# LVRegulation.net
KiCad netlist of a schematic drawn in Altium Designer
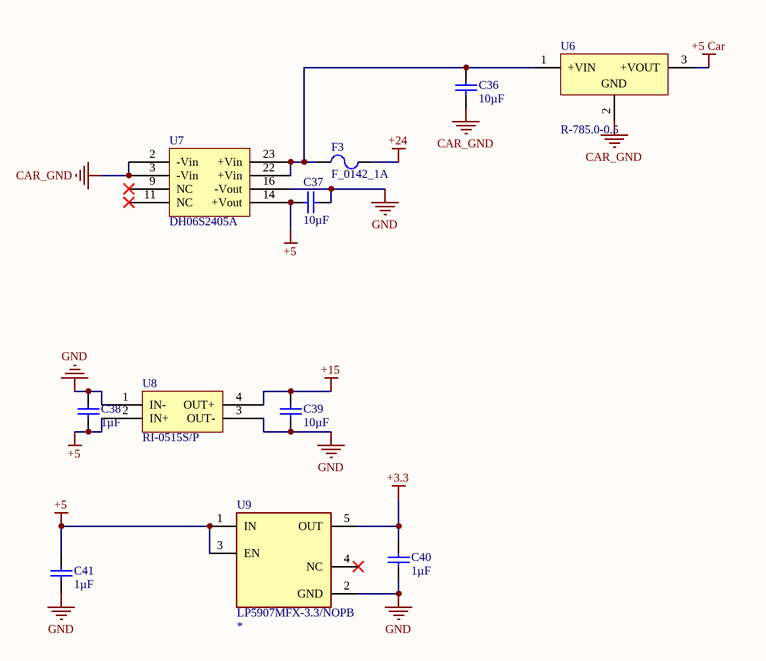
[diagram p0: LVRegulation.SchDoc]

(export (version "E")
  (design (tool "Eeschema 10.0.6"))
  (components
    (comp (ref "C36")
      (value "10µF")
      (footprint "1210_Capacitor")
      (description "Cap Cerem 10uF 10% 50V")
      (fields (field (name "TOLERANCE") "10%"))
      (libsource (lib "University of Minnesota - Solar Vehicle Project") (part "Cap"))
    )
    (comp (ref "C37")
      (value "10µF")
      (footprint "1210_Capacitor")
      (description "Cap Cerem 10uF 10% 50V")
      (fields (field (name "TOLERANCE") "10%"))
      (libsource (lib "University of Minnesota - Solar Vehicle Project") (part "Cap"))
    )
    (comp (ref "C38")
      (value "1µF")
      (footprint "0805_Capacitor")
      (description "CAP 0805 1uF 50V")
      (fields (field (name "TOLERANCE") "10%"))
      (libsource (lib "University of Minnesota - Solar Vehicle Project") (part "Cap"))
    )
    (comp (ref "C39")
      (value "10µF")
      (footprint "1210_Capacitor")
      (description "Cap Cerem 10uF 10% 50V")
      (fields (field (name "TOLERANCE") "10%"))
      (libsource (lib "University of Minnesota - Solar Vehicle Project") (part "Cap"))
    )
    (comp (ref "C40")
      (value "1µF")
      (footprint "0805_Capacitor")
      (description "CAP 0805 1uF 50V")
      (fields (field (name "TOLERANCE") "10%"))
      (libsource (lib "University of Minnesota - Solar Vehicle Project") (part "Cap"))
    )
    (comp (ref "C41")
      (value "1µF")
      (footprint "0805_Capacitor")
      (description "CAP 0805 1uF 50V")
      (fields (field (name "TOLERANCE") "10%"))
      (libsource (lib "University of Minnesota - Solar Vehicle Project") (part "Cap"))
    )
    (comp (ref "F3")
      (value "F_0142_1A")
      (footprint "0154_FUSE_HOLDER")
      (fields (field (name "SVP CREATOR") "Spencer Berglund"))
      (libsource (lib "University of Minnesota - Solar Vehicle Project") (part "F_0142_1A"))
    )
    (comp (ref "U6")
      (value "R-785.0-0.5")
      (footprint "REPO-R-78XX-3_V")
      (description "DC-DC Regulated Power Supply Module, 1 Output, 2.5W, Hybrid")
      (libsource (lib "University of Minnesota - Solar Vehicle Project") (part "REPO-R-78XX-3"))
    )
    (comp (ref "U7")
      (value "DH06S2405A")
      (footprint "DH06S2405A-Footprint-1")
      (description "DC/DC converter 18...75 VDC 5 VDC, DJ06S4805A, Delta-Electronics")
      (libsource (lib "University of Minnesota - Solar Vehicle Project") (part "DH06S2405A"))
    )
    (comp (ref "U8")
      (value "RI-0515S/P")
      (footprint "ROE-2405S-Footprint-1")
      (description "DC-DC Unregulated Power Supply Module, 1 Output, 2W, Hybrid")
      (libsource (lib "University of Minnesota - Solar Vehicle Project") (part "RI-0515S_P-Symbol-1"))
    )
    (comp (ref "U9")
      (value "LP5907MFX-3.3/NOPB")
      (footprint "FP-DBV0005A-MFG")
      (description "Fixed Positive LDO Regulator, 3.3V, 0.25V Dropout, PDSO5")
      (fields
        (field (name "MP") "LP5907MFX-3.0/NOPB")
        (field (name "ALTIUM_VALUE") "*")
        (field (name "MF") "Texas Instruments")
      )
      (libsource (lib "University of Minnesota - Solar Vehicle Project") (part "LP5907MFX-3.3/NOPB"))
    )
  )
  (nets
    (net (code "1") (name "+3.3") (class "Default")
      (node (ref "C40") (pin "2") (pinfunction "2_2") (pintype "passive"))
      (node (ref "U9") (pin "5") (pinfunction "OUT_5") (pintype "passive"))
    )
    (net (code "2") (name "+5") (class "Default")
      (node (ref "C37") (pin "1") (pinfunction "1_1") (pintype "passive"))
      (node (ref "C38") (pin "1") (pinfunction "1_1") (pintype "passive"))
      (node (ref "C41") (pin "2") (pinfunction "2_2") (pintype "passive"))
      (node (ref "U7") (pin "14") (pinfunction "+Vout_14") (pintype "power_in"))
      (node (ref "U8") (pin "2") (pinfunction "IN+_2") (pintype "passive"))
      (node (ref "U9") (pin "1") (pinfunction "IN_1") (pintype "passive"))
      (node (ref "U9") (pin "3") (pinfunction "EN_3") (pintype "passive"))
    )
    (net (code "3") (name "+5 Car") (class "Default")
      (node (ref "U6") (pin "3") (pinfunction "+VOUT_3") (pintype "power_in"))
    )
    (net (code "4") (name "+15") (class "Default")
      (node (ref "C39") (pin "2") (pinfunction "2_2") (pintype "passive"))
      (node (ref "U8") (pin "4") (pinfunction "OUT+_4") (pintype "passive"))
    )
    (net (code "5") (name "+24") (class "Default")
      (node (ref "F3") (pin "2") (pinfunction "2_2") (pintype "passive"))
    )
    (net (code "6") (name "CAR_GND") (class "Default")
      (node (ref "C36") (pin "1") (pinfunction "1_1") (pintype "passive"))
      (node (ref "U6") (pin "2") (pinfunction "GND_2") (pintype "power_in"))
      (node (ref "U7") (pin "2") (pinfunction "-Vin_2") (pintype "power_in"))
      (node (ref "U7") (pin "3") (pinfunction "-Vin_3") (pintype "power_in"))
    )
    (net (code "7") (name "GND") (class "Default")
      (node (ref "C37") (pin "2") (pinfunction "2_2") (pintype "passive"))
      (node (ref "C38") (pin "2") (pinfunction "2_2") (pintype "passive"))
      (node (ref "C39") (pin "1") (pinfunction "1_1") (pintype "passive"))
      (node (ref "C40") (pin "1") (pinfunction "1_1") (pintype "passive"))
      (node (ref "C41") (pin "1") (pinfunction "1_1") (pintype "passive"))
      (node (ref "U7") (pin "16") (pinfunction "-Vout_16") (pintype "power_in"))
      (node (ref "U8") (pin "1") (pinfunction "IN-_1") (pintype "passive"))
      (node (ref "U8") (pin "3") (pinfunction "OUT-_3") (pintype "passive"))
      (node (ref "U9") (pin "2") (pinfunction "GND_2") (pintype "power_in"))
    )
    (net (code "8") (name "Net-(U6-+VIN)") (class "Default")
      (node (ref "C36") (pin "2") (pinfunction "2_2") (pintype "passive"))
      (node (ref "F3") (pin "1") (pinfunction "1_1") (pintype "passive"))
      (node (ref "U6") (pin "1") (pinfunction "+VIN_1") (pintype "power_in"))
      (node (ref "U7") (pin "22") (pinfunction "+Vin_22") (pintype "power_in"))
      (node (ref "U7") (pin "23") (pinfunction "+Vin_23") (pintype "power_in"))
    )
    (net (code "9") (name "unconnected-(U7-NC-Pad9)") (class "Default")
      (node (ref "U7") (pin "9") (pinfunction "NC_9") (pintype "power_in+no_connect"))
    )
    (net (code "10") (name "unconnected-(U7-NC-Pad11)") (class "Default")
      (node (ref "U7") (pin "11") (pinfunction "NC_11") (pintype "power_in+no_connect"))
    )
    (net (code "11") (name "unconnected-(U9-NC-Pad4)") (class "Default")
      (node (ref "U9") (pin "4") (pinfunction "NC_4") (pintype "passive+no_connect"))
    )
  )
)
